# BeagleBoneCape.net
KiCad netlist of a schematic drawn in Altium Designer
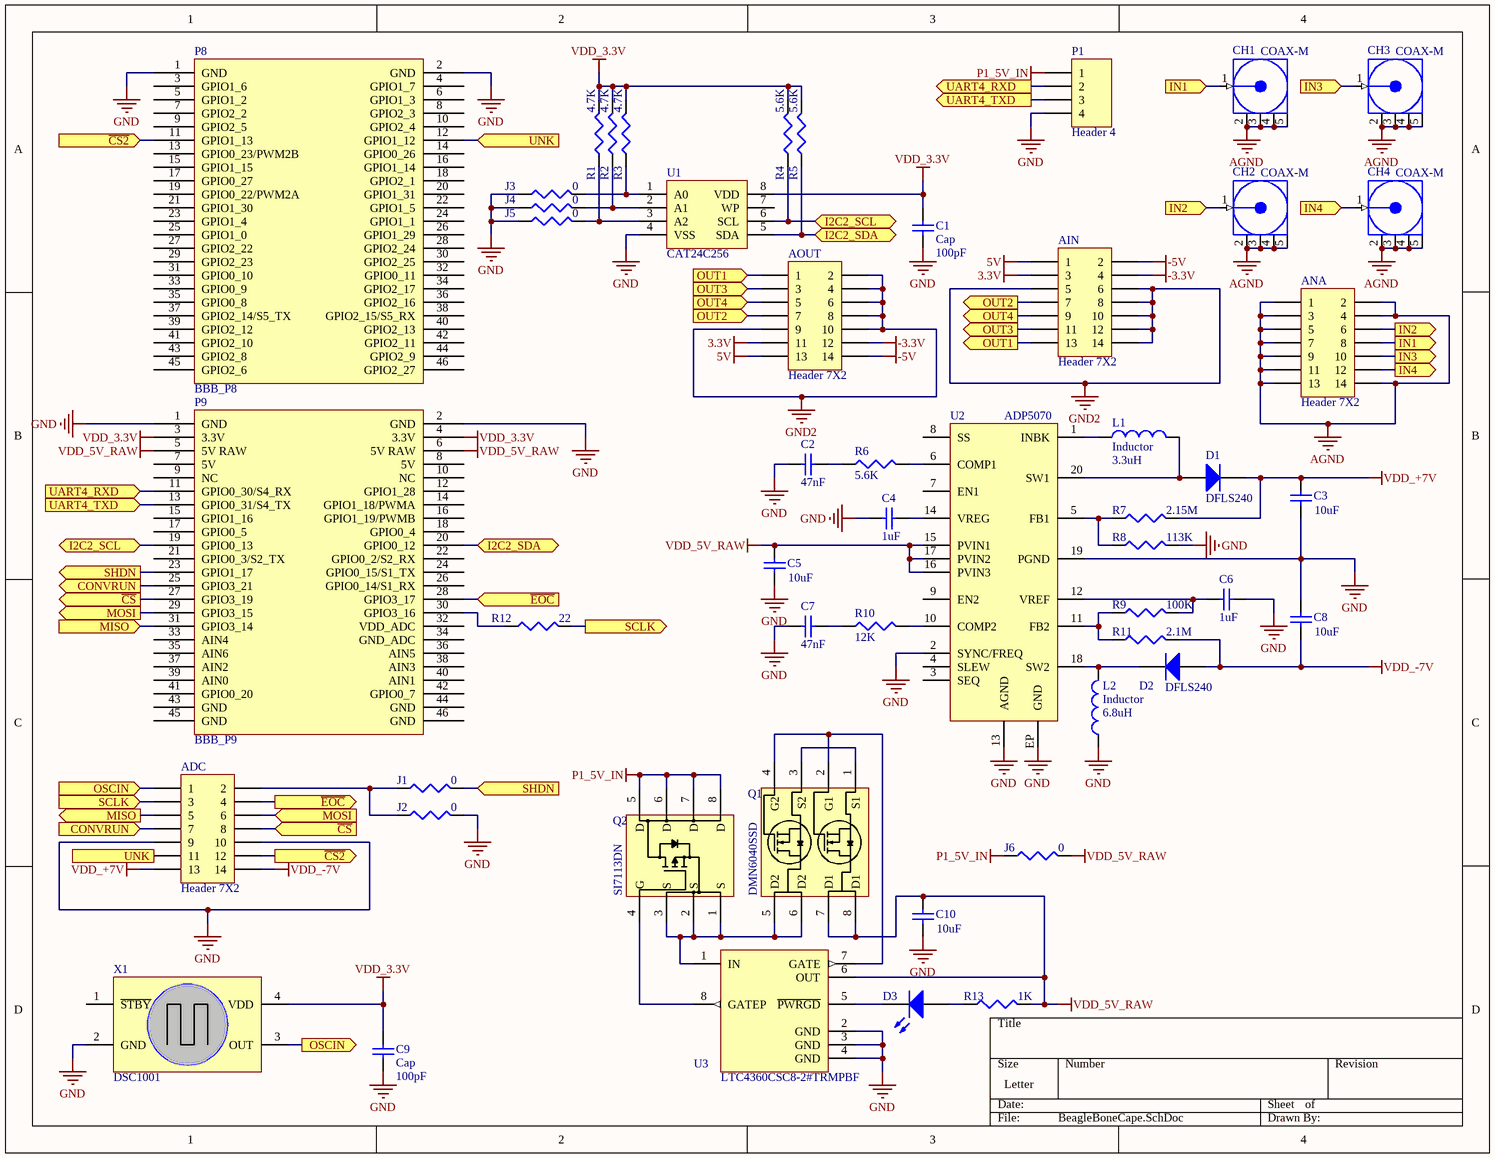
[diagram p0: BeagleBoneCape.SchDoc]

(export (version "E")
  (design (tool "Eeschema 10.0.6"))
  (components
    (comp (ref "ADC")
      (value "Header 7X2")
      (footprint "FLE-107-01-G-DV-A-TR")
      (description "Header, 7-Pin, Dual row")
      (fields (field (name "PUBLISHER") "Altium Limited"))
      (libsource (lib "Miscellaneous Connectors") (part "Header 7X2"))
    )
    (comp (ref "AIN")
      (value "Header 7X2")
      (footprint "FLE-107-01-G-DV-A-TR")
      (description "Header, 7-Pin, Dual row")
      (fields (field (name "PUBLISHER") "Altium Limited"))
      (libsource (lib "Miscellaneous Connectors") (part "Header 7X2"))
    )
    (comp (ref "ANA")
      (value "Header 7X2")
      (footprint "FLE-107-01-G-DV-A-TR")
      (description "Header, 7-Pin, Dual row")
      (fields (field (name "PUBLISHER") "Altium Limited"))
      (libsource (lib "Miscellaneous Connectors") (part "Header 7X2"))
    )
    (comp (ref "AOUT")
      (value "Header 7X2")
      (footprint "FLE-107-01-G-DV-A-TR")
      (description "Header, 7-Pin, Dual row")
      (fields (field (name "PUBLISHER") "Altium Limited"))
      (libsource (lib "Miscellaneous Connectors") (part "Header 7X2"))
    )
    (comp (ref "C1")
      (value "Cap")
      (footprint "1608[0603]")
      (description "Capacitor")
      (fields (field (name "ALTIUM_VALUE") "100pF") (field (name "PUBLISHER") "Altium Limited"))
      (libsource (lib "Miscellaneous Devices") (part "Cap"))
    )
    (comp (ref "C2")
      (value "47nF")
      (footprint "1608[0603]")
      (description "Capacitor")
      (fields (field (name "Comment") "Cap") (field (name "PUBLISHER") "Altium Limited"))
      (libsource (lib "Miscellaneous Devices") (part "Cap"))
    )
    (comp (ref "C3")
      (value "10uF")
      (footprint "1608[0603]")
      (description "Capacitor")
      (fields (field (name "Comment") "Cap") (field (name "PUBLISHER") "Altium Limited"))
      (libsource (lib "Miscellaneous Devices") (part "Cap"))
    )
    (comp (ref "C4")
      (value "1uF")
      (footprint "1608[0603]")
      (description "Capacitor")
      (fields (field (name "Comment") "Cap") (field (name "PUBLISHER") "Altium Limited"))
      (libsource (lib "Miscellaneous Devices") (part "Cap"))
    )
    (comp (ref "C5")
      (value "10uF")
      (footprint "14-1210")
      (description "Capacitor")
      (fields (field (name "Comment") "Cap") (field (name "PUBLISHER") "Altium Limited"))
      (libsource (lib "Miscellaneous Devices") (part "Cap"))
    )
    (comp (ref "C6")
      (value "1uF")
      (footprint "1608[0603]")
      (description "Capacitor")
      (fields (field (name "Comment") "Cap") (field (name "PUBLISHER") "Altium Limited"))
      (libsource (lib "Miscellaneous Devices") (part "Cap"))
    )
    (comp (ref "C7")
      (value "47nF")
      (footprint "1608[0603]")
      (description "Capacitor")
      (fields (field (name "Comment") "Cap") (field (name "PUBLISHER") "Altium Limited"))
      (libsource (lib "Miscellaneous Devices") (part "Cap"))
    )
    (comp (ref "C8")
      (value "10uF")
      (footprint "1608[0603]")
      (description "Capacitor")
      (fields (field (name "Comment") "Cap") (field (name "PUBLISHER") "Altium Limited"))
      (libsource (lib "Miscellaneous Devices") (part "Cap"))
    )
    (comp (ref "C9")
      (value "Cap")
      (footprint "1608[0603]")
      (description "Capacitor")
      (fields (field (name "ALTIUM_VALUE") "100pF") (field (name "PUBLISHER") "Altium Limited"))
      (libsource (lib "Miscellaneous Devices") (part "Cap"))
    )
    (comp (ref "C10")
      (value "10uF")
      (footprint "1608[0603]")
      (description "Capacitor")
      (fields (field (name "Comment") "Cap") (field (name "PUBLISHER") "Altium Limited"))
      (libsource (lib "Miscellaneous Devices") (part "Cap"))
    )
    (comp (ref "CH1")
      (value "COAX-M")
      (footprint "MMCX-J-P-H-ST-TH1")
      (description "RF Coaxial PCB Connector, MMCX; Thru-Hole, Vertical Mount Plug,  50 Ohm Impedance")
      (fields (field (name "PUBLISHER") "Altium Limited"))
      (libsource (lib "Miscellaneous Connectors") (part "COAX-M"))
    )
    (comp (ref "CH2")
      (value "COAX-M")
      (footprint "MMCX-J-P-H-ST-TH1")
      (description "RF Coaxial PCB Connector, MMCX; Thru-Hole, Vertical Mount Plug,  50 Ohm Impedance")
      (fields (field (name "PUBLISHER") "Altium Limited"))
      (libsource (lib "Miscellaneous Connectors") (part "COAX-M"))
    )
    (comp (ref "CH3")
      (value "COAX-M")
      (footprint "MMCX-J-P-H-ST-TH1")
      (description "RF Coaxial PCB Connector, MMCX; Thru-Hole, Vertical Mount Plug,  50 Ohm Impedance")
      (fields (field (name "PUBLISHER") "Altium Limited"))
      (libsource (lib "Miscellaneous Connectors") (part "COAX-M"))
    )
    (comp (ref "CH4")
      (value "COAX-M")
      (footprint "MMCX-J-P-H-ST-TH1")
      (description "RF Coaxial PCB Connector, MMCX; Thru-Hole, Vertical Mount Plug,  50 Ohm Impedance")
      (fields (field (name "PUBLISHER") "Altium Limited"))
      (libsource (lib "Miscellaneous Connectors") (part "COAX-M"))
    )
    (comp (ref "D1")
      (value "DFLS240")
      (footprint "DFLS240")
      (description "Default Diode")
      (fields (field (name "PUBLISHER") "Altium Limited"))
      (libsource (lib "Miscellaneous Devices") (part "Diode"))
    )
    (comp (ref "D2")
      (value "DFLS240")
      (footprint "DFLS240")
      (description "Default Diode")
      (fields (field (name "PUBLISHER") "Altium Limited"))
      (libsource (lib "Miscellaneous Devices") (part "Diode"))
    )
    (comp (ref "D3")
      (value "LED2")
      (footprint "1608[0603]")
      (description "Typical RED, GREEN, YELLOW, AMBER GaAs LED")
      (fields (field (name "PUBLISHER") "Altium Limited"))
      (libsource (lib "Miscellaneous Devices") (part "LED2"))
    )
    (comp (ref "J1")
      (value "0")
      (footprint "J1-0603")
      (description "Resistor")
      (fields (field (name "Comment") "Res3") (field (name "PUBLISHER") "Altium Limited"))
      (libsource (lib "Miscellaneous Devices") (part "Res3"))
    )
    (comp (ref "J2")
      (value "0")
      (footprint "J1-0603")
      (description "Resistor")
      (fields (field (name "Comment") "Res3") (field (name "PUBLISHER") "Altium Limited"))
      (libsource (lib "Miscellaneous Devices") (part "Res3"))
    )
    (comp (ref "J3")
      (value "0")
      (footprint "J1-0603")
      (description "Resistor")
      (fields (field (name "Comment") "Res3") (field (name "PUBLISHER") "Altium Limited"))
      (libsource (lib "Miscellaneous Devices") (part "Res3"))
    )
    (comp (ref "J4")
      (value "0")
      (footprint "J1-0603")
      (description "Resistor")
      (fields (field (name "Comment") "Res3") (field (name "PUBLISHER") "Altium Limited"))
      (libsource (lib "Miscellaneous Devices") (part "Res3"))
    )
    (comp (ref "J5")
      (value "0")
      (footprint "J1-0603")
      (description "Resistor")
      (fields (field (name "Comment") "Res3") (field (name "PUBLISHER") "Altium Limited"))
      (libsource (lib "Miscellaneous Devices") (part "Res3"))
    )
    (comp (ref "J6")
      (value "0")
      (footprint "14-1210")
      (description "Resistor")
      (fields (field (name "Comment") "Res3") (field (name "PUBLISHER") "Altium Limited"))
      (libsource (lib "Miscellaneous Devices") (part "Res3"))
    )
    (comp (ref "L1")
      (value "Inductor")
      (footprint "SMD_41_41_21")
      (fields (field (name "ALTIUM_VALUE") "3.3uH") (field (name "PUBLISHER") "Altium Limited"))
      (libsource (lib "Miscellaneous Devices") (part "Inductor"))
    )
    (comp (ref "L2")
      (value "Inductor")
      (footprint "SMD_41_41_31")
      (fields (field (name "ALTIUM_VALUE") "6.8uH") (field (name "PUBLISHER") "Altium Limited"))
      (libsource (lib "Miscellaneous Devices") (part "Inductor"))
    )
    (comp (ref "P1")
      (value "Header 4")
      (footprint "0705530038")
      (description "Header, 4-Pin")
      (fields (field (name "PUBLISHER") "Altium Limited"))
      (libsource (lib "Miscellaneous Connectors") (part "Header 4"))
    )
    (comp (ref "P8")
      (value "BBB_P8")
      (footprint "BBB_CAPE_HEADER")
      (libsource (lib "BeagleBoneCape") (part "BBB_P8"))
    )
    (comp (ref "P9")
      (value "BBB_P9")
      (footprint "BBB_CAPE_HEADER")
      (libsource (lib "BeagleBoneCape") (part "BBB_P9"))
    )
    (comp (ref "Q1")
      (value "DMN6040SSD")
      (footprint "SOIC-8")
      (libsource (lib "DMN6040SSD") (part "DMN6040SSD"))
    )
    (comp (ref "Q2")
      (value "SI7113DN")
      (footprint "PowerPAK1212-8")
      (libsource (lib "SI7113DN") (part "SI7113DN"))
    )
    (comp (ref "R1")
      (value "4.7K")
      (footprint "J1-0603")
      (description "Resistor")
      (fields (field (name "Comment") "Res3") (field (name "PUBLISHER") "Altium Limited"))
      (libsource (lib "Miscellaneous Devices") (part "Res3"))
    )
    (comp (ref "R2")
      (value "4.7K")
      (footprint "J1-0603")
      (description "Resistor")
      (fields (field (name "Comment") "Res3") (field (name "PUBLISHER") "Altium Limited"))
      (libsource (lib "Miscellaneous Devices") (part "Res3"))
    )
    (comp (ref "R3")
      (value "4.7K")
      (footprint "J1-0603")
      (description "Resistor")
      (fields (field (name "Comment") "Res3") (field (name "PUBLISHER") "Altium Limited"))
      (libsource (lib "Miscellaneous Devices") (part "Res3"))
    )
    (comp (ref "R4")
      (value "5.6K")
      (footprint "J1-0603")
      (description "Resistor")
      (fields (field (name "Comment") "Res3") (field (name "PUBLISHER") "Altium Limited"))
      (libsource (lib "Miscellaneous Devices") (part "Res3"))
    )
    (comp (ref "R5")
      (value "5.6K")
      (footprint "J1-0603")
      (description "Resistor")
      (fields (field (name "Comment") "Res3") (field (name "PUBLISHER") "Altium Limited"))
      (libsource (lib "Miscellaneous Devices") (part "Res3"))
    )
    (comp (ref "R6")
      (value "5.6K")
      (footprint "J1-0603")
      (description "Resistor")
      (fields (field (name "Comment") "Res3") (field (name "PUBLISHER") "Altium Limited"))
      (libsource (lib "Miscellaneous Devices") (part "Res3"))
    )
    (comp (ref "R7")
      (value "2.15M")
      (footprint "J1-0603")
      (description "Resistor")
      (fields (field (name "Comment") "Res3") (field (name "PUBLISHER") "Altium Limited"))
      (libsource (lib "Miscellaneous Devices") (part "Res3"))
    )
    (comp (ref "R8")
      (value "113K")
      (footprint "J1-0603")
      (description "Resistor")
      (fields (field (name "Comment") "Res3") (field (name "PUBLISHER") "Altium Limited"))
      (libsource (lib "Miscellaneous Devices") (part "Res3"))
    )
    (comp (ref "R9")
      (value "100K")
      (footprint "J1-0603")
      (description "Resistor")
      (fields (field (name "Comment") "Res3") (field (name "PUBLISHER") "Altium Limited"))
      (libsource (lib "Miscellaneous Devices") (part "Res3"))
    )
    (comp (ref "R10")
      (value "12K")
      (footprint "J1-0603")
      (description "Resistor")
      (fields (field (name "Comment") "Res3") (field (name "PUBLISHER") "Altium Limited"))
      (libsource (lib "Miscellaneous Devices") (part "Res3"))
    )
    (comp (ref "R11")
      (value "2.1M")
      (footprint "J1-0603")
      (description "Resistor")
      (fields (field (name "Comment") "Res3") (field (name "PUBLISHER") "Altium Limited"))
      (libsource (lib "Miscellaneous Devices") (part "Res3"))
    )
    (comp (ref "R12")
      (value "22")
      (footprint "J1-0603")
      (description "Resistor")
      (fields (field (name "Comment") "Res3") (field (name "PUBLISHER") "Altium Limited"))
      (libsource (lib "Miscellaneous Devices") (part "Res3"))
    )
    (comp (ref "R13")
      (value "1K")
      (footprint "J1-0603")
      (description "Resistor")
      (fields (field (name "Comment") "Res3") (field (name "PUBLISHER") "Altium Limited"))
      (libsource (lib "Miscellaneous Devices") (part "Res3"))
    )
    (comp (ref "U1")
      (value "CAT24C256")
      (footprint "SOIC-8")
      (libsource (lib "BeagleBoneCape") (part "CAT24C256"))
    )
    (comp (ref "U2")
      (value "ADP5070")
      (footprint "QFN50P400X400X80_HS-21N")
      (libsource (lib "ADP5070") (part "ADP5070"))
    )
    (comp (ref "U3")
      (value "LTC4360CSC8-2#TRMPBF")
      (footprint "LT-SC8-8-SC70_N")
      (fields (field (name "MANUFACTURER") "Linear Technology"))
      (libsource (lib "Linear Technology Power Management Hot Swap Controllers") (part "LTC4360CSC8-2#TRMPBF"))
    )
    (comp (ref "X1") (value "DSC1001") (footprint "DSC1001") (libsource (lib "DSC1001") (part "DSC1001")))
  )
  (nets
    (net (code "1") (name "-3.3V") (class "Default")
      (node (ref "AIN") (pin "4") (pinfunction "4_4") (pintype "passive"))
      (node (ref "AOUT") (pin "12") (pinfunction "12_12") (pintype "passive"))
    )
    (net (code "2") (name "-5V") (class "Default")
      (node (ref "AIN") (pin "2") (pinfunction "2_2") (pintype "passive"))
      (node (ref "AOUT") (pin "14") (pinfunction "14_14") (pintype "passive"))
    )
    (net (code "3") (name "/CONVRUN") (class "Default")
      (node (ref "ADC") (pin "7") (pinfunction "7_7") (pintype "passive"))
      (node (ref "P9") (pin "25") (pinfunction "GPIO3_21_25") (pintype "passive"))
    )
    (net (code "4") (name "/I2C2_SCL") (class "Default")
      (node (ref "P9") (pin "19") (pinfunction "GPIO0_13_19") (pintype "passive"))
      (node (ref "R4") (pin "1") (pinfunction "1_1") (pintype "passive"))
      (node (ref "U1") (pin "6") (pinfunction "SCL_6") (pintype "passive"))
    )
    (net (code "5") (name "/I2C2_SDA") (class "Default")
      (node (ref "P9") (pin "20") (pinfunction "GPIO0_12_20") (pintype "passive"))
      (node (ref "R5") (pin "1") (pinfunction "1_1") (pintype "passive"))
      (node (ref "U1") (pin "5") (pinfunction "SDA_5") (pintype "passive"))
    )
    (net (code "6") (name "/IN1") (class "Default")
      (node (ref "ANA") (pin "8") (pinfunction "8_8") (pintype "passive"))
      (node (ref "CH1") (pin "1") (pinfunction "Signal_1") (pintype "input"))
    )
    (net (code "7") (name "/IN2") (class "Default")
      (node (ref "ANA") (pin "6") (pinfunction "6_6") (pintype "passive"))
      (node (ref "CH2") (pin "1") (pinfunction "Signal_1") (pintype "input"))
    )
    (net (code "8") (name "/IN3") (class "Default")
      (node (ref "ANA") (pin "10") (pinfunction "10_10") (pintype "passive"))
      (node (ref "CH3") (pin "1") (pinfunction "Signal_1") (pintype "input"))
    )
    (net (code "9") (name "/IN4") (class "Default")
      (node (ref "ANA") (pin "12") (pinfunction "12_12") (pintype "passive"))
      (node (ref "CH4") (pin "1") (pinfunction "Signal_1") (pintype "input"))
    )
    (net (code "10") (name "/MISO") (class "Default")
      (node (ref "ADC") (pin "5") (pinfunction "5_5") (pintype "passive"))
      (node (ref "P9") (pin "31") (pinfunction "GPIO3_14_31") (pintype "passive"))
    )
    (net (code "11") (name "/MOSI") (class "Default")
      (node (ref "ADC") (pin "6") (pinfunction "6_6") (pintype "passive"))
      (node (ref "P9") (pin "29") (pinfunction "GPIO3_15_29") (pintype "passive"))
    )
    (net (code "12") (name "/OSCIN") (class "Default")
      (node (ref "ADC") (pin "1") (pinfunction "1_1") (pintype "passive"))
      (node (ref "X1") (pin "3") (pinfunction "OUT_3") (pintype "passive"))
    )
    (net (code "13") (name "/OUT1") (class "Default")
      (node (ref "AIN") (pin "13") (pinfunction "13_13") (pintype "passive"))
      (node (ref "AOUT") (pin "1") (pinfunction "1_1") (pintype "passive"))
    )
    (net (code "14") (name "/OUT2") (class "Default")
      (node (ref "AIN") (pin "7") (pinfunction "7_7") (pintype "passive"))
      (node (ref "AOUT") (pin "7") (pinfunction "7_7") (pintype "passive"))
    )
    (net (code "15") (name "/OUT3") (class "Default")
      (node (ref "AIN") (pin "11") (pinfunction "11_11") (pintype "passive"))
      (node (ref "AOUT") (pin "3") (pinfunction "3_3") (pintype "passive"))
    )
    (net (code "16") (name "/OUT4") (class "Default")
      (node (ref "AIN") (pin "9") (pinfunction "9_9") (pintype "passive"))
      (node (ref "AOUT") (pin "5") (pinfunction "5_5") (pintype "passive"))
    )
    (net (code "17") (name "/SCLK") (class "Default")
      (node (ref "ADC") (pin "3") (pinfunction "3_3") (pintype "passive"))
      (node (ref "R12") (pin "2") (pinfunction "2_2") (pintype "passive"))
    )
    (net (code "18") (name "/SHDN") (class "Default")
      (node (ref "J1") (pin "2") (pinfunction "2_2") (pintype "passive"))
      (node (ref "P9") (pin "23") (pinfunction "GPIO1_17_23") (pintype "passive"))
    )
    (net (code "19") (name "/UART4_RXD") (class "Default")
      (node (ref "P1") (pin "2") (pinfunction "2_2") (pintype "passive"))
      (node (ref "P9") (pin "11") (pinfunction "GPIO0_30/S4_RX_11") (pintype "passive"))
    )
    (net (code "20") (name "/UART4_TXD") (class "Default")
      (node (ref "P1") (pin "3") (pinfunction "3_3") (pintype "passive"))
      (node (ref "P9") (pin "13") (pinfunction "GPIO0_31/S4_TX_13") (pintype "passive"))
    )
    (net (code "21") (name "/UNK") (class "Default")
      (node (ref "ADC") (pin "11") (pinfunction "11_11") (pintype "passive"))
      (node (ref "P8") (pin "12") (pinfunction "GPIO1_12_12") (pintype "passive"))
    )
    (net (code "22") (name "/~{CS2}") (class "Default")
      (node (ref "ADC") (pin "12") (pinfunction "12_12") (pintype "passive"))
      (node (ref "P8") (pin "11") (pinfunction "GPIO1_13_11") (pintype "passive"))
    )
    (net (code "23") (name "/~{CS}") (class "Default")
      (node (ref "ADC") (pin "8") (pinfunction "8_8") (pintype "passive"))
      (node (ref "P9") (pin "27") (pinfunction "GPIO3_19_27") (pintype "passive"))
    )
    (net (code "24") (name "/~{EOC}") (class "Default")
      (node (ref "ADC") (pin "4") (pinfunction "4_4") (pintype "passive"))
      (node (ref "P9") (pin "28") (pinfunction "GPIO3_17_28") (pintype "passive"))
    )
    (net (code "25") (name "3.3V") (class "Default")
      (node (ref "AIN") (pin "3") (pinfunction "3_3") (pintype "passive"))
      (node (ref "AOUT") (pin "11") (pinfunction "11_11") (pintype "passive"))
    )
    (net (code "26") (name "5V") (class "Default")
      (node (ref "AIN") (pin "1") (pinfunction "1_1") (pintype "passive"))
      (node (ref "AOUT") (pin "13") (pinfunction "13_13") (pintype "passive"))
    )
    (net (code "27") (name "AGND") (class "Default")
      (node (ref "ANA") (pin "1") (pinfunction "1_1") (pintype "passive"))
      (node (ref "ANA") (pin "11") (pinfunction "11_11") (pintype "passive"))
      (node (ref "ANA") (pin "13") (pinfunction "13_13") (pintype "passive"))
      (node (ref "ANA") (pin "14") (pinfunction "14_14") (pintype "passive"))
      (node (ref "ANA") (pin "2") (pinfunction "2_2") (pintype "passive"))
      (node (ref "ANA") (pin "3") (pinfunction "3_3") (pintype "passive"))
      (node (ref "ANA") (pin "4") (pinfunction "4_4") (pintype "passive"))
      (node (ref "ANA") (pin "5") (pinfunction "5_5") (pintype "passive"))
      (node (ref "ANA") (pin "7") (pinfunction "7_7") (pintype "passive"))
      (node (ref "ANA") (pin "9") (pinfunction "9_9") (pintype "passive"))
      (node (ref "CH1") (pin "2") (pinfunction "GND_2") (pintype "power_in"))
      (node (ref "CH1") (pin "3") (pinfunction "GND_3") (pintype "power_in"))
      (node (ref "CH1") (pin "4") (pinfunction "GND_4") (pintype "power_in"))
      (node (ref "CH1") (pin "5") (pinfunction "GND_5") (pintype "power_in"))
      (node (ref "CH2") (pin "2") (pinfunction "GND_2") (pintype "power_in"))
      (node (ref "CH2") (pin "3") (pinfunction "GND_3") (pintype "power_in"))
      (node (ref "CH2") (pin "4") (pinfunction "GND_4") (pintype "power_in"))
      (node (ref "CH2") (pin "5") (pinfunction "GND_5") (pintype "power_in"))
      (node (ref "CH3") (pin "2") (pinfunction "GND_2") (pintype "power_in"))
      (node (ref "CH3") (pin "3") (pinfunction "GND_3") (pintype "power_in"))
      (node (ref "CH3") (pin "4") (pinfunction "GND_4") (pintype "power_in"))
      (node (ref "CH3") (pin "5") (pinfunction "GND_5") (pintype "power_in"))
      (node (ref "CH4") (pin "2") (pinfunction "GND_2") (pintype "power_in"))
      (node (ref "CH4") (pin "3") (pinfunction "GND_3") (pintype "power_in"))
      (node (ref "CH4") (pin "4") (pinfunction "GND_4") (pintype "power_in"))
      (node (ref "CH4") (pin "5") (pinfunction "GND_5") (pintype "power_in"))
    )
    (net (code "28") (name "GND") (class "Default")
      (node (ref "ADC") (pin "10") (pinfunction "10_10") (pintype "passive"))
      (node (ref "ADC") (pin "9") (pinfunction "9_9") (pintype "passive"))
      (node (ref "C1") (pin "1") (pinfunction "1_1") (pintype "passive"))
      (node (ref "C10") (pin "1") (pinfunction "1_1") (pintype "passive"))
      (node (ref "C2") (pin "2") (pinfunction "2_2") (pintype "passive"))
      (node (ref "C3") (pin "1") (pinfunction "1_1") (pintype "passive"))
      (node (ref "C4") (pin "2") (pinfunction "2_2") (pintype "passive"))
      (node (ref "C5") (pin "1") (pinfunction "1_1") (pintype "passive"))
      (node (ref "C6") (pin "1") (pinfunction "1_1") (pintype "passive"))
      (node (ref "C7") (pin "2") (pinfunction "2_2") (pintype "passive"))
      (node (ref "C8") (pin "2") (pinfunction "2_2") (pintype "passive"))
      (node (ref "C9") (pin "1") (pinfunction "1_1") (pintype "passive"))
      (node (ref "J2") (pin "2") (pinfunction "2_2") (pintype "passive"))
      (node (ref "J3") (pin "1") (pinfunction "1_1") (pintype "passive"))
      (node (ref "J4") (pin "1") (pinfunction "1_1") (pintype "passive"))
      (node (ref "J5") (pin "1") (pinfunction "1_1") (pintype "passive"))
      (node (ref "L2") (pin "1") (pinfunction "1_1") (pintype "passive"))
      (node (ref "P1") (pin "4") (pinfunction "4_4") (pintype "passive"))
      (node (ref "P8") (pin "1") (pinfunction "GND_1") (pintype "passive"))
      (node (ref "P8") (pin "2") (pinfunction "GND_2") (pintype "passive"))
      (node (ref "P9") (pin "1") (pinfunction "GND_1") (pintype "passive"))
      (node (ref "P9") (pin "2") (pinfunction "GND_2") (pintype "passive"))
      (node (ref "R8") (pin "2") (pinfunction "2_2") (pintype "passive"))
      (node (ref "U1") (pin "4") (pinfunction "VSS_4") (pintype "passive"))
      (node (ref "U2") (pin "13") (pinfunction "AGND_13") (pintype "passive"))
      (node (ref "U2") (pin "19") (pinfunction "PGND_19") (pintype "passive"))
      (node (ref "U2") (pin "2") (pinfunction "SYNC/FREQ_2") (pintype "passive"))
      (node (ref "U2") (pin "EP") (pinfunction "GND_EP") (pintype "passive"))
      (node (ref "U3") (pin "2") (pinfunction "GND_2") (pintype "power_in"))
      (node (ref "U3") (pin "3") (pinfunction "GND_3") (pintype "power_in"))
      (node (ref "U3") (pin "4") (pinfunction "GND_4") (pintype "power_in"))
      (node (ref "X1") (pin "2") (pinfunction "GND_2") (pintype "passive"))
    )
    (net (code "29") (name "GND2") (class "Default")
      (node (ref "AIN") (pin "10") (pinfunction "10_10") (pintype "passive"))
      (node (ref "AIN") (pin "12") (pinfunction "12_12") (pintype "passive"))
      (node (ref "AIN") (pin "14") (pinfunction "14_14") (pintype "passive"))
      (node (ref "AIN") (pin "5") (pinfunction "5_5") (pintype "passive"))
      (node (ref "AIN") (pin "6") (pinfunction "6_6") (pintype "passive"))
      (node (ref "AIN") (pin "8") (pinfunction "8_8") (pintype "passive"))
      (node (ref "AOUT") (pin "10") (pinfunction "10_10") (pintype "passive"))
      (node (ref "AOUT") (pin "2") (pinfunction "2_2") (pintype "passive"))
      (node (ref "AOUT") (pin "4") (pinfunction "4_4") (pintype "passive"))
      (node (ref "AOUT") (pin "6") (pinfunction "6_6") (pintype "passive"))
      (node (ref "AOUT") (pin "8") (pinfunction "8_8") (pintype "passive"))
      (node (ref "AOUT") (pin "9") (pinfunction "9_9") (pintype "passive"))
    )
    (net (code "30") (name "Net-(ADC-Pad2)") (class "Default")
      (node (ref "ADC") (pin "2") (pinfunction "2_2") (pintype "passive"))
      (node (ref "J1") (pin "1") (pinfunction "1_1") (pintype "passive"))
      (node (ref "J2") (pin "1") (pinfunction "1_1") (pintype "passive"))
    )
    (net (code "31") (name "Net-(C2-Pad1)") (class "Default")
      (node (ref "C2") (pin "1") (pinfunction "1_1") (pintype "passive"))
      (node (ref "R6") (pin "1") (pinfunction "1_1") (pintype "passive"))
    )
    (net (code "32") (name "Net-(C7-Pad1)") (class "Default")
      (node (ref "C7") (pin "1") (pinfunction "1_1") (pintype "passive"))
      (node (ref "R10") (pin "1") (pinfunction "1_1") (pintype "passive"))
    )
    (net (code "33") (name "Net-(D1-A)") (class "Default")
      (node (ref "D1") (pin "1") (pinfunction "A_1") (pintype "passive"))
      (node (ref "L1") (pin "2") (pinfunction "2_2") (pintype "passive"))
      (node (ref "U2") (pin "20") (pinfunction "SW1_20") (pintype "passive"))
    )
    (net (code "34") (name "Net-(D2-K)") (class "Default")
      (node (ref "D2") (pin "2") (pinfunction "K_2") (pintype "passive"))
      (node (ref "L2") (pin "2") (pinfunction "2_2") (pintype "passive"))
      (node (ref "U2") (pin "18") (pinfunction "SW2_18") (pintype "passive"))
    )
    (net (code "35") (name "Net-(D3-A)") (class "Default")
      (node (ref "D3") (pin "1") (pinfunction "A_1") (pintype "passive"))
      (node (ref "R13") (pin "1") (pinfunction "1_1") (pintype "passive"))
    )
    (net (code "36") (name "Net-(D3-K)") (class "Default")
      (node (ref "D3") (pin "2") (pinfunction "K_2") (pintype "passive"))
      (node (ref "U3") (pin "5") (pinfunction "~{PWRGD}_5") (pintype "tri_state"))
    )
    (net (code "37") (name "Net-(P9-GPIO3_16)") (class "Default")
      (node (ref "P9") (pin "30") (pinfunction "GPIO3_16_30") (pintype "passive"))
      (node (ref "R12") (pin "1") (pinfunction "1_1") (pintype "passive"))
    )
    (net (code "38") (name "Net-(Q1-G1)") (class "Default")
      (node (ref "Q1") (pin "2") (pinfunction "G1_2") (pintype "passive"))
      (node (ref "Q1") (pin "4") (pinfunction "G2_4") (pintype "passive"))
      (node (ref "U3") (pin "7") (pinfunction "GATE_7") (pintype "output"))
    )
    (net (code "39") (name "Net-(Q1-S1)") (class "Default")
      (node (ref "Q1") (pin "1") (pinfunction "S1_1") (pintype "passive"))
      (node (ref "Q1") (pin "3") (pinfunction "S2_3") (pintype "passive"))
    )
    (net (code "40") (name "Net-(Q2-G)") (class "Default")
      (node (ref "Q2") (pin "4") (pinfunction "G_4") (pintype "passive"))
      (node (ref "U3") (pin "8") (pinfunction "GATEP_8") (pintype "output"))
    )
    (net (code "41") (name "Net-(U1-A0)") (class "Default")
      (node (ref "J3") (pin "2") (pinfunction "2_2") (pintype "passive"))
      (node (ref "R3") (pin "1") (pinfunction "1_1") (pintype "passive"))
      (node (ref "U1") (pin "1") (pinfunction "A0_1") (pintype "passive"))
    )
    (net (code "42") (name "Net-(U1-A1)") (class "Default")
      (node (ref "J4") (pin "2") (pinfunction "2_2") (pintype "passive"))
      (node (ref "R2") (pin "1") (pinfunction "1_1") (pintype "passive"))
      (node (ref "U1") (pin "2") (pinfunction "A1_2") (pintype "passive"))
    )
    (net (code "43") (name "Net-(U1-A2)") (class "Default")
      (node (ref "J5") (pin "2") (pinfunction "2_2") (pintype "passive"))
      (node (ref "R1") (pin "1") (pinfunction "1_1") (pintype "passive"))
      (node (ref "U1") (pin "3") (pinfunction "A2_3") (pintype "passive"))
    )
    (net (code "44") (name "Net-(U2-COMP1)") (class "Default")
      (node (ref "R6") (pin "2") (pinfunction "2_2") (pintype "passive"))
      (node (ref "U2") (pin "6") (pinfunction "COMP1_6") (pintype "passive"))
    )
    (net (code "45") (name "Net-(U2-COMP2)") (class "Default")
      (node (ref "R10") (pin "2") (pinfunction "2_2") (pintype "passive"))
      (node (ref "U2") (pin "10") (pinfunction "COMP2_10") (pintype "passive"))
    )
    (net (code "46") (name "Net-(U2-FB1)") (class "Default")
      (node (ref "R7") (pin "1") (pinfunction "1_1") (pintype "passive"))
      (node (ref "R8") (pin "1") (pinfunction "1_1") (pintype "passive"))
      (node (ref "U2") (pin "5") (pinfunction "FB1_5") (pintype "passive"))
    )
    (net (code "47") (name "Net-(U2-FB2)") (class "Default")
      (node (ref "R11") (pin "1") (pinfunction "1_1") (pintype "passive"))
      (node (ref "R9") (pin "1") (pinfunction "1_1") (pintype "passive"))
      (node (ref "U2") (pin "11") (pinfunction "FB2_11") (pintype "passive"))
    )
    (net (code "48") (name "Net-(U2-INBK)") (class "Default")
      (node (ref "L1") (pin "1") (pinfunction "1_1") (pintype "passive"))
      (node (ref "U2") (pin "1") (pinfunction "INBK_1") (pintype "passive"))
    )
    (net (code "49") (name "Net-(U2-VREF)") (class "Default")
      (node (ref "C6") (pin "2") (pinfunction "2_2") (pintype "passive"))
      (node (ref "R9") (pin "2") (pinfunction "2_2") (pintype "passive"))
      (node (ref "U2") (pin "12") (pinfunction "VREF_12") (pintype "passive"))
    )
    (net (code "50") (name "Net-(U2-VREG)") (class "Default")
      (node (ref "C4") (pin "1") (pinfunction "1_1") (pintype "passive"))
      (node (ref "U2") (pin "14") (pinfunction "VREG_14") (pintype "passive"))
    )
    (net (code "51") (name "Net-(U3-IN)") (class "Default")
      (node (ref "Q1") (pin "5") (pinfunction "D2_5") (pintype "passive"))
      (node (ref "Q1") (pin "6") (pinfunction "D2_6") (pintype "passive"))
      (node (ref "Q2") (pin "1") (pinfunction "S_1") (pintype "passive"))
      (node (ref "Q2") (pin "2") (pinfunction "S_2") (pintype "passive"))
      (node (ref "Q2") (pin "3") (pinfunction "S_3") (pintype "passive"))
      (node (ref "U3") (pin "1") (pinfunction "IN_1") (pintype "power_in"))
    )
    (net (code "52") (name "P1_5V_IN") (class "Default")
      (node (ref "J6") (pin "1") (pinfunction "1_1") (pintype "passive"))
      (node (ref "P1") (pin "1") (pinfunction "1_1") (pintype "passive"))
      (node (ref "Q2") (pin "5") (pinfunction "D_5") (pintype "passive"))
      (node (ref "Q2") (pin "6") (pinfunction "D_6") (pintype "passive"))
      (node (ref "Q2") (pin "7") (pinfunction "D_7") (pintype "passive"))
      (node (ref "Q2") (pin "8") (pinfunction "D_8") (pintype "passive"))
    )
    (net (code "53") (name "VDD_+7V") (class "Default")
      (node (ref "ADC") (pin "13") (pinfunction "13_13") (pintype "passive"))
      (node (ref "C3") (pin "2") (pinfunction "2_2") (pintype "passive"))
      (node (ref "D1") (pin "2") (pinfunction "K_2") (pintype "passive"))
      (node (ref "R7") (pin "2") (pinfunction "2_2") (pintype "passive"))
    )
    (net (code "54") (name "VDD_-7V") (class "Default")
      (node (ref "ADC") (pin "14") (pinfunction "14_14") (pintype "passive"))
      (node (ref "C8") (pin "1") (pinfunction "1_1") (pintype "passive"))
      (node (ref "D2") (pin "1") (pinfunction "A_1") (pintype "passive"))
      (node (ref "R11") (pin "2") (pinfunction "2_2") (pintype "passive"))
    )
    (net (code "55") (name "VDD_3.3V") (class "Default")
      (node (ref "C1") (pin "2") (pinfunction "2_2") (pintype "passive"))
      (node (ref "C9") (pin "2") (pinfunction "2_2") (pintype "passive"))
      (node (ref "P9") (pin "3") (pinfunction "3.3V_3") (pintype "passive"))
      (node (ref "P9") (pin "4") (pinfunction "3.3V_4") (pintype "passive"))
      (node (ref "R1") (pin "2") (pinfunction "2_2") (pintype "passive"))
      (node (ref "R2") (pin "2") (pinfunction "2_2") (pintype "passive"))
      (node (ref "R3") (pin "2") (pinfunction "2_2") (pintype "passive"))
      (node (ref "R4") (pin "2") (pinfunction "2_2") (pintype "passive"))
      (node (ref "R5") (pin "2") (pinfunction "2_2") (pintype "passive"))
      (node (ref "U1") (pin "8") (pinfunction "VDD_8") (pintype "passive"))
      (node (ref "X1") (pin "4") (pinfunction "VDD_4") (pintype "passive"))
    )
    (net (code "56") (name "VDD_5V_RAW") (class "Default")
      (node (ref "C10") (pin "2") (pinfunction "2_2") (pintype "passive"))
      (node (ref "C5") (pin "2") (pinfunction "2_2") (pintype "passive"))
      (node (ref "J6") (pin "2") (pinfunction "2_2") (pintype "passive"))
      (node (ref "P9") (pin "5") (pinfunction "5V_RAW_5") (pintype "passive"))
      (node (ref "P9") (pin "6") (pinfunction "5V_RAW_6") (pintype "passive"))
      (node (ref "Q1") (pin "7") (pinfunction "D1_7") (pintype "passive"))
      (node (ref "Q1") (pin "8") (pinfunction "D1_8") (pintype "passive"))
      (node (ref "R13") (pin "2") (pinfunction "2_2") (pintype "passive"))
      (node (ref "U2") (pin "15") (pinfunction "PVIN1_15") (pintype "passive"))
      (node (ref "U2") (pin "16") (pinfunction "PVIN3_16") (pintype "passive"))
      (node (ref "U2") (pin "17") (pinfunction "PVIN2_17") (pintype "passive"))
      (node (ref "U3") (pin "6") (pinfunction "OUT_6") (pintype "power_in"))
    )
    (net (code "57") (name "unconnected-(P8-GPIO0_8-Pad35)") (class "Default")
      (node (ref "P8") (pin "35") (pinfunction "GPIO0_8_35") (pintype "passive"))
    )
    (net (code "58") (name "unconnected-(P8-GPIO0_9-Pad33)") (class "Default")
      (node (ref "P8") (pin "33") (pinfunction "GPIO0_9_33") (pintype "passive"))
    )
    (net (code "59") (name "unconnected-(P8-GPIO0_10-Pad31)") (class "Default")
      (node (ref "P8") (pin "31") (pinfunction "GPIO0_10_31") (pintype "passive"))
    )
    (net (code "60") (name "unconnected-(P8-GPIO0_11-Pad32)") (class "Default")
      (node (ref "P8") (pin "32") (pinfunction "GPIO0_11_32") (pintype "passive"))
    )
    (net (code "61") (name "unconnected-(P8-GPIO0_22{slash}PWM2A-Pad19)") (class "Default")
      (node (ref "P8") (pin "19") (pinfunction "GPIO0_22/PWM2A_19") (pintype "passive"))
    )
    (net (code "62") (name "unconnected-(P8-GPIO0_23{slash}PWM2B-Pad13)") (class "Default")
      (node (ref "P8") (pin "13") (pinfunction "GPIO0_23/PWM2B_13") (pintype "passive"))
    )
    (net (code "63") (name "unconnected-(P8-GPIO0_26-Pad14)") (class "Default")
      (node (ref "P8") (pin "14") (pinfunction "GPIO0_26_14") (pintype "passive"))
    )
    (net (code "64") (name "unconnected-(P8-GPIO0_27-Pad17)") (class "Default")
      (node (ref "P8") (pin "17") (pinfunction "GPIO0_27_17") (pintype "passive"))
    )
    (net (code "65") (name "unconnected-(P8-GPIO1_0-Pad25)") (class "Default")
      (node (ref "P8") (pin "25") (pinfunction "GPIO1_0_25") (pintype "passive"))
    )
    (net (code "66") (name "unconnected-(P8-GPIO1_1-Pad24)") (class "Default")
      (node (ref "P8") (pin "24") (pinfunction "GPIO1_1_24") (pintype "passive"))
    )
    (net (code "67") (name "unconnected-(P8-GPIO1_2-Pad5)") (class "Default")
      (node (ref "P8") (pin "5") (pinfunction "GPIO1_2_5") (pintype "passive"))
    )
    (net (code "68") (name "unconnected-(P8-GPIO1_3-Pad6)") (class "Default")
      (node (ref "P8") (pin "6") (pinfunction "GPIO1_3_6") (pintype "passive"))
    )
    (net (code "69") (name "unconnected-(P8-GPIO1_4-Pad23)") (class "Default")
      (node (ref "P8") (pin "23") (pinfunction "GPIO1_4_23") (pintype "passive"))
    )
    (net (code "70") (name "unconnected-(P8-GPIO1_5-Pad22)") (class "Default")
      (node (ref "P8") (pin "22") (pinfunction "GPIO1_5_22") (pintype "passive"))
    )
    (net (code "71") (name "unconnected-(P8-GPIO1_6-Pad3)") (class "Default")
      (node (ref "P8") (pin "3") (pinfunction "GPIO1_6_3") (pintype "passive"))
    )
    (net (code "72") (name "unconnected-(P8-GPIO1_7-Pad4)") (class "Default")
      (node (ref "P8") (pin "4") (pinfunction "GPIO1_7_4") (pintype "passive"))
    )
    (net (code "73") (name "unconnected-(P8-GPIO1_14-Pad16)") (class "Default")
      (node (ref "P8") (pin "16") (pinfunction "GPIO1_14_16") (pintype "passive"))
    )
    (net (code "74") (name "unconnected-(P8-GPIO1_15-Pad15)") (class "Default")
      (node (ref "P8") (pin "15") (pinfunction "GPIO1_15_15") (pintype "passive"))
    )
    (net (code "75") (name "unconnected-(P8-GPIO1_29-Pad26)") (class "Default")
      (node (ref "P8") (pin "26") (pinfunction "GPIO1_29_26") (pintype "passive"))
    )
    (net (code "76") (name "unconnected-(P8-GPIO1_30-Pad21)") (class "Default")
      (node (ref "P8") (pin "21") (pinfunction "GPIO1_30_21") (pintype "passive"))
    )
    (net (code "77") (name "unconnected-(P8-GPIO1_31-Pad20)") (class "Default")
      (node (ref "P8") (pin "20") (pinfunction "GPIO1_31_20") (pintype "passive"))
    )
    (net (code "78") (name "unconnected-(P8-GPIO2_1-Pad18)") (class "Default")
      (node (ref "P8") (pin "18") (pinfunction "GPIO2_1_18") (pintype "passive"))
    )
    (net (code "79") (name "unconnected-(P8-GPIO2_2-Pad7)") (class "Default")
      (node (ref "P8") (pin "7") (pinfunction "GPIO2_2_7") (pintype "passive"))
    )
    (net (code "80") (name "unconnected-(P8-GPIO2_3-Pad8)") (class "Default")
      (node (ref "P8") (pin "8") (pinfunction "GPIO2_3_8") (pintype "passive"))
    )
    (net (code "81") (name "unconnected-(P8-GPIO2_4-Pad10)") (class "Default")
      (node (ref "P8") (pin "10") (pinfunction "GPIO2_4_10") (pintype "passive"))
    )
    (net (code "82") (name "unconnected-(P8-GPIO2_5-Pad9)") (class "Default")
      (node (ref "P8") (pin "9") (pinfunction "GPIO2_5_9") (pintype "passive"))
    )
    (net (code "83") (name "unconnected-(P8-GPIO2_6-Pad45)") (class "Default")
      (node (ref "P8") (pin "45") (pinfunction "GPIO2_6_45") (pintype "passive"))
    )
    (net (code "84") (name "unconnected-(P8-GPIO2_8-Pad43)") (class "Default")
      (node (ref "P8") (pin "43") (pinfunction "GPIO2_8_43") (pintype "passive"))
    )
    (net (code "85") (name "unconnected-(P8-GPIO2_9-Pad44)") (class "Default")
      (node (ref "P8") (pin "44") (pinfunction "GPIO2_9_44") (pintype "passive"))
    )
    (net (code "86") (name "unconnected-(P8-GPIO2_10-Pad41)") (class "Default")
      (node (ref "P8") (pin "41") (pinfunction "GPIO2_10_41") (pintype "passive"))
    )
    (net (code "87") (name "unconnected-(P8-GPIO2_11-Pad42)") (class "Default")
      (node (ref "P8") (pin "42") (pinfunction "GPIO2_11_42") (pintype "passive"))
    )
    (net (code "88") (name "unconnected-(P8-GPIO2_12-Pad39)") (class "Default")
      (node (ref "P8") (pin "39") (pinfunction "GPIO2_12_39") (pintype "passive"))
    )
    (net (code "89") (name "unconnected-(P8-GPIO2_13-Pad40)") (class "Default")
      (node (ref "P8") (pin "40") (pinfunction "GPIO2_13_40") (pintype "passive"))
    )
    (net (code "90") (name "unconnected-(P8-GPIO2_14{slash}S5_TX-Pad37)") (class "Default")
      (node (ref "P8") (pin "37") (pinfunction "GPIO2_14/S5_TX_37") (pintype "passive"))
    )
    (net (code "91") (name "unconnected-(P8-GPIO2_15{slash}S5_RX-Pad38)") (class "Default")
      (node (ref "P8") (pin "38") (pinfunction "GPIO2_15/S5_RX_38") (pintype "passive"))
    )
    (net (code "92") (name "unconnected-(P8-GPIO2_16-Pad36)") (class "Default")
      (node (ref "P8") (pin "36") (pinfunction "GPIO2_16_36") (pintype "passive"))
    )
    (net (code "93") (name "unconnected-(P8-GPIO2_17-Pad34)") (class "Default")
      (node (ref "P8") (pin "34") (pinfunction "GPIO2_17_34") (pintype "passive"))
    )
    (net (code "94") (name "unconnected-(P8-GPIO2_22-Pad27)") (class "Default")
      (node (ref "P8") (pin "27") (pinfunction "GPIO2_22_27") (pintype "passive"))
    )
    (net (code "95") (name "unconnected-(P8-GPIO2_23-Pad29)") (class "Default")
      (node (ref "P8") (pin "29") (pinfunction "GPIO2_23_29") (pintype "passive"))
    )
    (net (code "96") (name "unconnected-(P8-GPIO2_24-Pad28)") (class "Default")
      (node (ref "P8") (pin "28") (pinfunction "GPIO2_24_28") (pintype "passive"))
    )
    (net (code "97") (name "unconnected-(P8-GPIO2_25-Pad30)") (class "Default")
      (node (ref "P8") (pin "30") (pinfunction "GPIO2_25_30") (pintype "passive"))
    )
    (net (code "98") (name "unconnected-(P8-GPIO2_27-Pad46)") (class "Default")
      (node (ref "P8") (pin "46") (pinfunction "GPIO2_27_46") (pintype "passive"))
    )
    (net (code "99") (name "unconnected-(P9-5V-Pad7)") (class "Default")
      (node (ref "P9") (pin "7") (pinfunction "5V_7") (pintype "passive"))
    )
    (net (code "100") (name "unconnected-(P9-5V-Pad8)") (class "Default")
      (node (ref "P9") (pin "8") (pinfunction "5V_8") (pintype "passive"))
    )
    (net (code "101") (name "unconnected-(P9-AIN0-Pad39)") (class "Default")
      (node (ref "P9") (pin "39") (pinfunction "AIN0_39") (pintype "passive"))
    )
    (net (code "102") (name "unconnected-(P9-AIN1-Pad40)") (class "Default")
      (node (ref "P9") (pin "40") (pinfunction "AIN1_40") (pintype "passive"))
    )
    (net (code "103") (name "unconnected-(P9-AIN2-Pad37)") (class "Default")
      (node (ref "P9") (pin "37") (pinfunction "AIN2_37") (pintype "passive"))
    )
    (net (code "104") (name "unconnected-(P9-AIN3-Pad38)") (class "Default")
      (node (ref "P9") (pin "38") (pinfunction "AIN3_38") (pintype "passive"))
    )
    (net (code "105") (name "unconnected-(P9-AIN4-Pad33)") (class "Default")
      (node (ref "P9") (pin "33") (pinfunction "AIN4_33") (pintype "passive"))
    )
    (net (code "106") (name "unconnected-(P9-AIN5-Pad36)") (class "Default")
      (node (ref "P9") (pin "36") (pinfunction "AIN5_36") (pintype "passive"))
    )
    (net (code "107") (name "unconnected-(P9-AIN6-Pad35)") (class "Default")
      (node (ref "P9") (pin "35") (pinfunction "AIN6_35") (pintype "passive"))
    )
    (net (code "108") (name "unconnected-(P9-GND-Pad43)") (class "Default")
      (node (ref "P9") (pin "43") (pinfunction "GND_43") (pintype "passive"))
    )
    (net (code "109") (name "unconnected-(P9-GND-Pad44)") (class "Default")
      (node (ref "P9") (pin "44") (pinfunction "GND_44") (pintype "passive"))
    )
    (net (code "110") (name "unconnected-(P9-GND-Pad45)") (class "Default")
      (node (ref "P9") (pin "45") (pinfunction "GND_45") (pintype "passive"))
    )
    (net (code "111") (name "unconnected-(P9-GND-Pad46)") (class "Default")
      (node (ref "P9") (pin "46") (pinfunction "GND_46") (pintype "passive"))
    )
    (net (code "112") (name "unconnected-(P9-GND_ADC-Pad34)") (class "Default")
      (node (ref "P9") (pin "34") (pinfunction "GND_ADC_34") (pintype "passive"))
    )
    (net (code "113") (name "unconnected-(P9-GPIO0_2{slash}S2_RX-Pad22)") (class "Default")
      (node (ref "P9") (pin "22") (pinfunction "GPIO0_2/S2_RX_22") (pintype "passive"))
    )
    (net (code "114") (name "unconnected-(P9-GPIO0_3{slash}S2_TX-Pad21)") (class "Default")
      (node (ref "P9") (pin "21") (pinfunction "GPIO0_3/S2_TX_21") (pintype "passive"))
    )
    (net (code "115") (name "unconnected-(P9-GPIO0_4-Pad18)") (class "Default")
      (node (ref "P9") (pin "18") (pinfunction "GPIO0_4_18") (pintype "passive"))
    )
    (net (code "116") (name "unconnected-(P9-GPIO0_5-Pad17)") (class "Default")
      (node (ref "P9") (pin "17") (pinfunction "GPIO0_5_17") (pintype "passive"))
    )
    (net (code "117") (name "unconnected-(P9-GPIO0_7-Pad42)") (class "Default")
      (node (ref "P9") (pin "42") (pinfunction "GPIO0_7_42") (pintype "passive"))
    )
    (net (code "118") (name "unconnected-(P9-GPIO0_14{slash}S1_RX-Pad26)") (class "Default")
      (node (ref "P9") (pin "26") (pinfunction "GPIO0_14/S1_RX_26") (pintype "passive"))
    )
    (net (code "119") (name "unconnected-(P9-GPIO0_15{slash}S1_TX-Pad24)") (class "Default")
      (node (ref "P9") (pin "24") (pinfunction "GPIO0_15/S1_TX_24") (pintype "passive"))
    )
    (net (code "120") (name "unconnected-(P9-GPIO0_20-Pad41)") (class "Default")
      (node (ref "P9") (pin "41") (pinfunction "GPIO0_20_41") (pintype "passive"))
    )
    (net (code "121") (name "unconnected-(P9-GPIO1_16-Pad15)") (class "Default")
      (node (ref "P9") (pin "15") (pinfunction "GPIO1_16_15") (pintype "passive"))
    )
    (net (code "122") (name "unconnected-(P9-GPIO1_18{slash}PWMA-Pad14)") (class "Default")
      (node (ref "P9") (pin "14") (pinfunction "GPIO1_18/PWMA_14") (pintype "passive"))
    )
    (net (code "123") (name "unconnected-(P9-GPIO1_19{slash}PWMB-Pad16)") (class "Default")
      (node (ref "P9") (pin "16") (pinfunction "GPIO1_19/PWMB_16") (pintype "passive"))
    )
    (net (code "124") (name "unconnected-(P9-GPIO1_28-Pad12)") (class "Default")
      (node (ref "P9") (pin "12") (pinfunction "GPIO1_28_12") (pintype "passive"))
    )
    (net (code "125") (name "unconnected-(P9-NC-Pad9)") (class "Default")
      (node (ref "P9") (pin "9") (pinfunction "NC_9") (pintype "passive"))
    )
    (net (code "126") (name "unconnected-(P9-NC-Pad10)") (class "Default")
      (node (ref "P9") (pin "10") (pinfunction "NC_10") (pintype "passive"))
    )
    (net (code "127") (name "unconnected-(P9-VDD_ADC-Pad32)") (class "Default")
      (node (ref "P9") (pin "32") (pinfunction "VDD_ADC_32") (pintype "passive"))
    )
    (net (code "128") (name "unconnected-(U1-WP-Pad7)") (class "Default")
      (node (ref "U1") (pin "7") (pinfunction "WP_7") (pintype "passive"))
    )
    (net (code "129") (name "unconnected-(U2-EN1-Pad7)") (class "Default")
      (node (ref "U2") (pin "7") (pinfunction "EN1_7") (pintype "passive"))
    )
    (net (code "130") (name "unconnected-(U2-EN2-Pad9)") (class "Default")
      (node (ref "U2") (pin "9") (pinfunction "EN2_9") (pintype "passive"))
    )
    (net (code "131") (name "unconnected-(U2-SEQ-Pad3)") (class "Default")
      (node (ref "U2") (pin "3") (pinfunction "SEQ_3") (pintype "passive"))
    )
    (net (code "132") (name "unconnected-(U2-SLEW-Pad4)") (class "Default")
      (node (ref "U2") (pin "4") (pinfunction "SLEW_4") (pintype "passive"))
    )
    (net (code "133") (name "unconnected-(U2-SS-Pad8)") (class "Default")
      (node (ref "U2") (pin "8") (pinfunction "SS_8") (pintype "passive"))
    )
    (net (code "134") (name "unconnected-(X1-~{STBY}-Pad1)") (class "Default")
      (node (ref "X1") (pin "1") (pinfunction "~{STBY}_1") (pintype "passive"))
    )
  )
)
